# hurf1_board.net
KiCad netlist of a schematic drawn in EAGLE
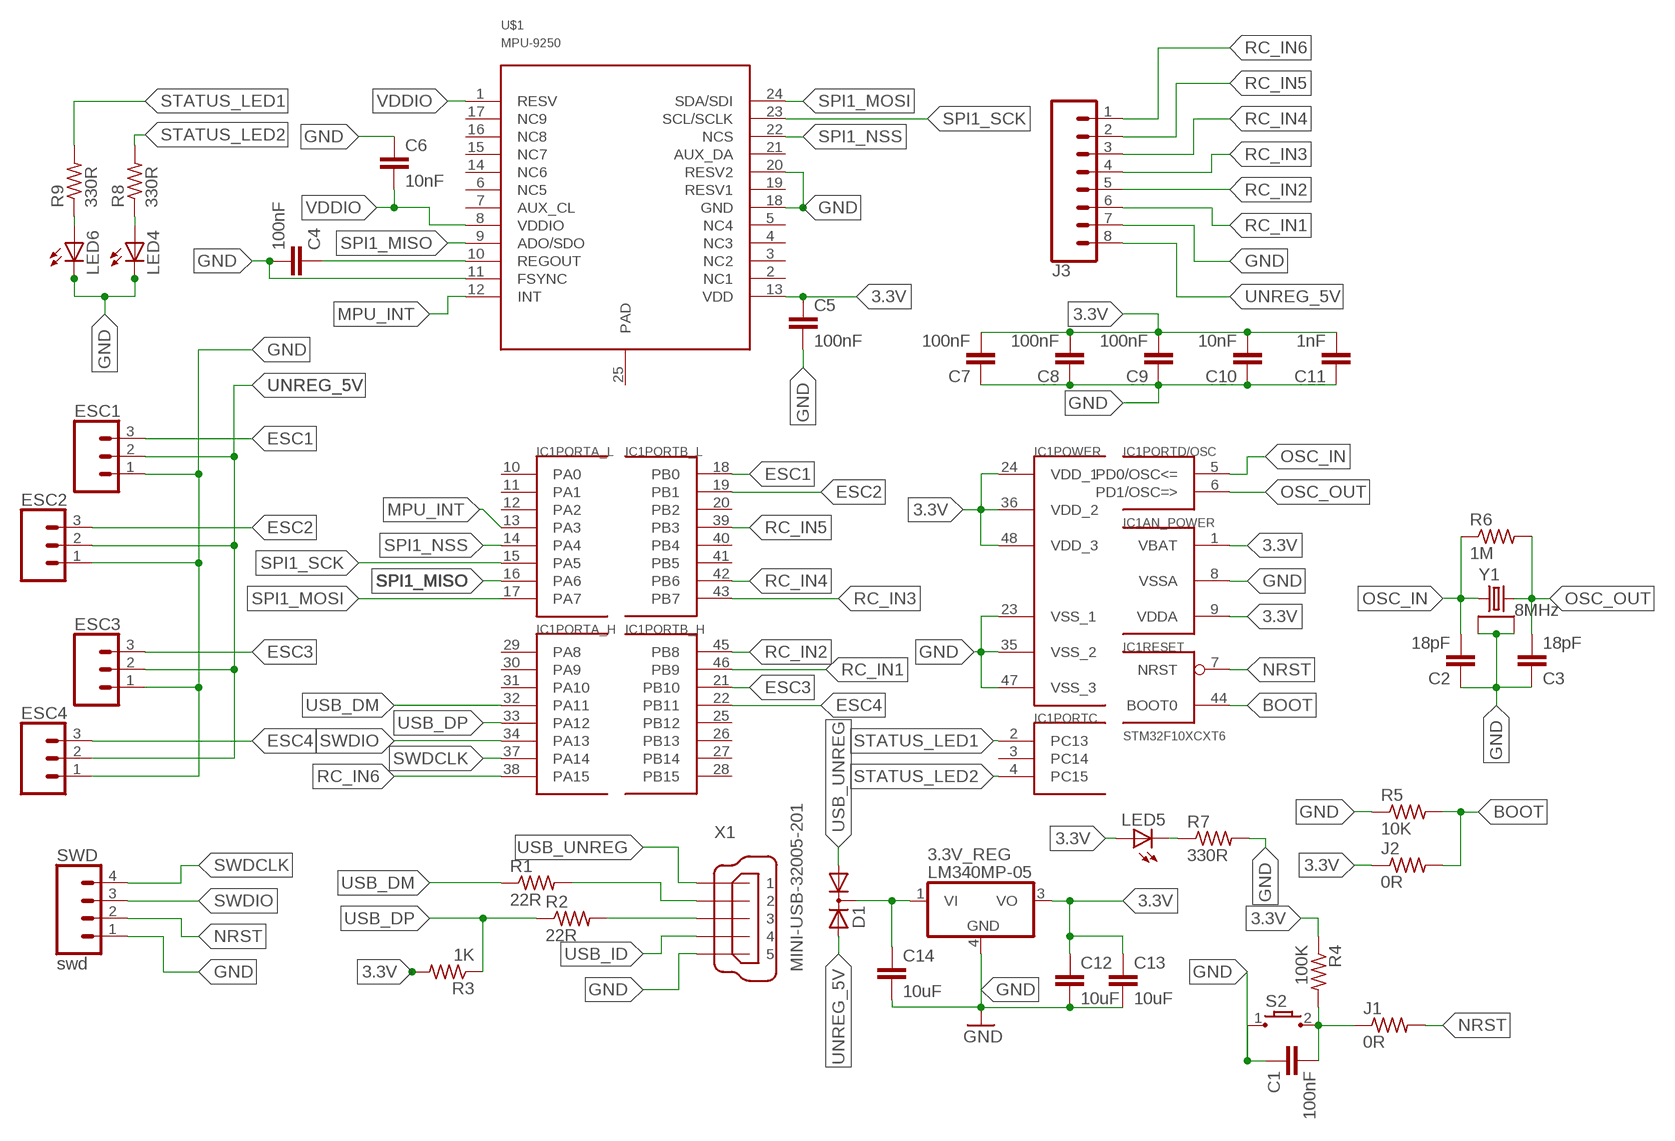
[diagram p0: schematic, sheet 1]

(export (version "E")
  (design (tool "Eeschema 10.0.6"))
  (components
    (comp (ref "3.3V_REG")
      (value "LM340MP-05")
      (footprint "eagle-import:SOT223")
      (libsource (lib "eagle-import") (part "LM340?-MP05"))
    )
    (comp (ref "C1")
      (value "100nF")
      (footprint "eagle-import:C0603")
      (libsource (lib "eagle-import") (part "C-EUC0603"))
    )
    (comp (ref "C2")
      (value "18pF")
      (footprint "eagle-import:C0603")
      (libsource (lib "eagle-import") (part "C-EUC0603"))
    )
    (comp (ref "C3")
      (value "18pF")
      (footprint "eagle-import:C0603")
      (libsource (lib "eagle-import") (part "C-EUC0603"))
    )
    (comp (ref "C4")
      (value "100nF")
      (footprint "eagle-import:C0805K")
      (libsource (lib "eagle-import") (part "resistor_348_C-EUC0805K"))
    )
    (comp (ref "C5")
      (value "100nF")
      (footprint "eagle-import:C0603")
      (libsource (lib "eagle-import") (part "C-EUC0603"))
    )
    (comp (ref "C6")
      (value "10nF")
      (footprint "eagle-import:C0603")
      (libsource (lib "eagle-import") (part "C-EUC0603"))
    )
    (comp (ref "C7")
      (value "100nF")
      (footprint "eagle-import:C0603")
      (libsource (lib "eagle-import") (part "C-EUC0603"))
    )
    (comp (ref "C8")
      (value "100nF")
      (footprint "eagle-import:C0603")
      (libsource (lib "eagle-import") (part "C-EUC0603"))
    )
    (comp (ref "C9")
      (value "100nF")
      (footprint "eagle-import:C0603")
      (libsource (lib "eagle-import") (part "C-EUC0603"))
    )
    (comp (ref "C10")
      (value "10nF")
      (footprint "eagle-import:C0603")
      (libsource (lib "eagle-import") (part "C-EUC0603"))
    )
    (comp (ref "C11")
      (value "1nF")
      (footprint "eagle-import:C0603")
      (libsource (lib "eagle-import") (part "C-EUC0603"))
    )
    (comp (ref "C12")
      (value "10uF")
      (footprint "eagle-import:C0805")
      (libsource (lib "eagle-import") (part "C-EUC0805"))
    )
    (comp (ref "C13")
      (value "10uF")
      (footprint "eagle-import:C0805")
      (libsource (lib "eagle-import") (part "C-EUC0805"))
    )
    (comp (ref "C14")
      (value "10uF")
      (footprint "eagle-import:C0805")
      (libsource (lib "eagle-import") (part "C-EUC0805"))
    )
    (comp (ref "D1")
      (value "DIODE-2AC|CASOT23")
      (footprint "eagle-import:SOT23")
      (libsource (lib "eagle-import") (part "DIODE-2AC|CASOT23"))
    )
    (comp (ref "ESC1")
      (value "CONN_03")
      (footprint "eagle-import:1X03")
      (libsource (lib "eagle-import") (part "CONN_03"))
    )
    (comp (ref "ESC2")
      (value "CONN_03")
      (footprint "eagle-import:1X03")
      (libsource (lib "eagle-import") (part "CONN_03"))
    )
    (comp (ref "ESC3")
      (value "CONN_03")
      (footprint "eagle-import:1X03")
      (libsource (lib "eagle-import") (part "CONN_03"))
    )
    (comp (ref "ESC4")
      (value "CONN_03")
      (footprint "eagle-import:1X03")
      (libsource (lib "eagle-import") (part "CONN_03"))
    )
    (comp (ref "IC1")
      (value "STM32F10XCXT6")
      (footprint "eagle-import:TQFP48")
      (libsource (lib "eagle-import") (part "STM32F10XCXT6"))
    )
    (comp (ref "J1")
      (value "0R")
      (footprint "eagle-import:R0603")
      (libsource (lib "eagle-import") (part "R-US_R0603"))
    )
    (comp (ref "J2")
      (value "0R")
      (footprint "eagle-import:R0603")
      (libsource (lib "eagle-import") (part "R-US_R0603"))
    )
    (comp (ref "J3")
      (value "CONN_08")
      (footprint "eagle-import:1X08_1MM_RA")
      (libsource (lib "eagle-import") (part "CONN_08"))
    )
    (comp (ref "LED4")
      (value "LEDSML0805")
      (footprint "eagle-import:SML0805")
      (libsource (lib "eagle-import") (part "LEDSML0805"))
    )
    (comp (ref "LED5")
      (value "LEDSML0805")
      (footprint "eagle-import:SML0805")
      (libsource (lib "eagle-import") (part "LEDSML0805"))
    )
    (comp (ref "LED6")
      (value "LEDSML0805")
      (footprint "eagle-import:SML0805")
      (libsource (lib "eagle-import") (part "LEDSML0805"))
    )
    (comp (ref "R1")
      (value "22R")
      (footprint "eagle-import:R0603")
      (libsource (lib "eagle-import") (part "R-US_R0603"))
    )
    (comp (ref "R2")
      (value "22R")
      (footprint "eagle-import:R0603")
      (libsource (lib "eagle-import") (part "R-US_R0603"))
    )
    (comp (ref "R3")
      (value "1K")
      (footprint "eagle-import:R0603")
      (libsource (lib "eagle-import") (part "R-US_R0603"))
    )
    (comp (ref "R4")
      (value "100K")
      (footprint "eagle-import:R0603")
      (libsource (lib "eagle-import") (part "R-US_R0603"))
    )
    (comp (ref "R5")
      (value "10K")
      (footprint "eagle-import:R0603")
      (libsource (lib "eagle-import") (part "R-US_R0603"))
    )
    (comp (ref "R6")
      (value "1M")
      (footprint "eagle-import:R0603")
      (libsource (lib "eagle-import") (part "R-US_R0603"))
    )
    (comp (ref "R7")
      (value "330R")
      (footprint "eagle-import:R0603")
      (libsource (lib "eagle-import") (part "R-US_R0603"))
    )
    (comp (ref "R8")
      (value "330R")
      (footprint "eagle-import:R0603")
      (libsource (lib "eagle-import") (part "R-US_R0603"))
    )
    (comp (ref "R9")
      (value "330R")
      (footprint "eagle-import:R0603")
      (libsource (lib "eagle-import") (part "R-US_R0603"))
    )
    (comp (ref "S2")
      (value "TL3302-G")
      (footprint "eagle-import:TL3302_GULL_WING")
      (libsource (lib "eagle-import") (part "TL3302-G"))
    )
    (comp (ref "SWD")
      (value "swd")
      (footprint "eagle-import:1X04_1MM_RA")
      (libsource (lib "eagle-import") (part "CONN_04SMD2"))
    )
    (comp (ref "U$1")
      (value "MPU-9250")
      (footprint "eagle-import:LEAD-QFN24")
      (libsource (lib "eagle-import") (part "MPU-9250"))
    )
    (comp (ref "X1")
      (value "MINI-USB-32005-201")
      (footprint "eagle-import:32005-201")
      (libsource (lib "eagle-import") (part "MINI-USB-32005-201"))
    )
    (comp (ref "Y1")
      (value "8MHz")
      (footprint "eagle-import:GSX-531")
      (libsource (lib "eagle-import") (part "GSX-531"))
    )
  )
  (nets
    (net (code "1") (name "3.3V") (class "Default")
      (node (ref "3.3V_REG") (pin "3") (pinfunction "VO_3") (pintype "passive"))
      (node (ref "C10") (pin "2") (pinfunction "2_2") (pintype "passive"))
      (node (ref "C11") (pin "2") (pinfunction "2_2") (pintype "passive"))
      (node (ref "C12") (pin "1") (pinfunction "1_1") (pintype "passive"))
      (node (ref "C13") (pin "1") (pinfunction "1_1") (pintype "passive"))
      (node (ref "C5") (pin "1") (pinfunction "1_1") (pintype "passive"))
      (node (ref "C7") (pin "2") (pinfunction "2_2") (pintype "passive"))
      (node (ref "C8") (pin "2") (pinfunction "2_2") (pintype "passive"))
      (node (ref "C9") (pin "2") (pinfunction "2_2") (pintype "passive"))
      (node (ref "IC1") (pin "1") (pinfunction "VBAT_1") (pintype "power_in"))
      (node (ref "IC1") (pin "24") (pinfunction "VDD_1_24") (pintype "power_in"))
      (node (ref "IC1") (pin "36") (pinfunction "VDD_2_36") (pintype "power_in"))
      (node (ref "IC1") (pin "48") (pinfunction "VDD_3_48") (pintype "power_in"))
      (node (ref "IC1") (pin "9") (pinfunction "VDDA_9") (pintype "power_in"))
      (node (ref "J2") (pin "1") (pinfunction "1_1") (pintype "passive"))
      (node (ref "LED5") (pin "A") (pinfunction "A_A") (pintype "passive"))
      (node (ref "R3") (pin "2") (pinfunction "2_2") (pintype "passive"))
      (node (ref "R4") (pin "1") (pinfunction "1_1") (pintype "passive"))
      (node (ref "U$1") (pin "13") (pinfunction "VDD_13") (pintype "bidirectional"))
    )
    (net (code "2") (name "BOOT") (class "Default")
      (node (ref "IC1") (pin "44") (pinfunction "BOOT0_44") (pintype "input"))
      (node (ref "J2") (pin "2") (pinfunction "2_2") (pintype "passive"))
      (node (ref "R5") (pin "2") (pinfunction "2_2") (pintype "passive"))
    )
    (net (code "3") (name "ESC1") (class "Default")
      (node (ref "ESC1") (pin "3") (pinfunction "3_3") (pintype "passive"))
      (node (ref "IC1") (pin "18") (pinfunction "PB0_18") (pintype "bidirectional"))
    )
    (net (code "4") (name "ESC2") (class "Default")
      (node (ref "ESC2") (pin "3") (pinfunction "3_3") (pintype "passive"))
      (node (ref "IC1") (pin "19") (pinfunction "PB1_19") (pintype "bidirectional"))
    )
    (net (code "5") (name "ESC3") (class "Default")
      (node (ref "ESC3") (pin "3") (pinfunction "3_3") (pintype "passive"))
      (node (ref "IC1") (pin "21") (pinfunction "PB10_21") (pintype "bidirectional"))
    )
    (net (code "6") (name "ESC4") (class "Default")
      (node (ref "ESC4") (pin "3") (pinfunction "3_3") (pintype "passive"))
      (node (ref "IC1") (pin "22") (pinfunction "PB11_22") (pintype "bidirectional"))
    )
    (net (code "7") (name "GND") (class "Default")
      (node (ref "3.3V_REG") (pin "4") (pinfunction "GND_4") (pintype "passive"))
      (node (ref "C1") (pin "1") (pinfunction "1_1") (pintype "passive"))
      (node (ref "C10") (pin "1") (pinfunction "1_1") (pintype "passive"))
      (node (ref "C11") (pin "1") (pinfunction "1_1") (pintype "passive"))
      (node (ref "C12") (pin "2") (pinfunction "2_2") (pintype "passive"))
      (node (ref "C13") (pin "2") (pinfunction "2_2") (pintype "passive"))
      (node (ref "C14") (pin "2") (pinfunction "2_2") (pintype "passive"))
      (node (ref "C2") (pin "1") (pinfunction "1_1") (pintype "passive"))
      (node (ref "C3") (pin "1") (pinfunction "1_1") (pintype "passive"))
      (node (ref "C4") (pin "2") (pinfunction "2_2") (pintype "passive"))
      (node (ref "C5") (pin "2") (pinfunction "2_2") (pintype "passive"))
      (node (ref "C6") (pin "1") (pinfunction "1_1") (pintype "passive"))
      (node (ref "C7") (pin "1") (pinfunction "1_1") (pintype "passive"))
      (node (ref "C8") (pin "1") (pinfunction "1_1") (pintype "passive"))
      (node (ref "C9") (pin "1") (pinfunction "1_1") (pintype "passive"))
      (node (ref "ESC1") (pin "1") (pinfunction "1_1") (pintype "passive"))
      (node (ref "ESC2") (pin "1") (pinfunction "1_1") (pintype "passive"))
      (node (ref "ESC3") (pin "1") (pinfunction "1_1") (pintype "passive"))
      (node (ref "ESC4") (pin "1") (pinfunction "1_1") (pintype "passive"))
      (node (ref "IC1") (pin "23") (pinfunction "VSS_1_23") (pintype "power_in"))
      (node (ref "IC1") (pin "35") (pinfunction "VSS_2_35") (pintype "power_in"))
      (node (ref "IC1") (pin "47") (pinfunction "VSS_3_47") (pintype "power_in"))
      (node (ref "IC1") (pin "8") (pinfunction "VSSA_8") (pintype "power_in"))
      (node (ref "J3") (pin "7") (pinfunction "7_7") (pintype "passive"))
      (node (ref "LED4") (pin "C") (pinfunction "C_C") (pintype "passive"))
      (node (ref "LED6") (pin "C") (pinfunction "C_C") (pintype "passive"))
      (node (ref "R5") (pin "1") (pinfunction "1_1") (pintype "passive"))
      (node (ref "R7") (pin "2") (pinfunction "2_2") (pintype "passive"))
      (node (ref "S2") (pin "1") (pinfunction "1_1") (pintype "passive"))
      (node (ref "SWD") (pin "1") (pinfunction "1_1") (pintype "passive"))
      (node (ref "U$1") (pin "11") (pinfunction "FSYNC_11") (pintype "bidirectional"))
      (node (ref "U$1") (pin "18") (pinfunction "GND_18") (pintype "bidirectional"))
      (node (ref "U$1") (pin "20") (pinfunction "RESV2_20") (pintype "bidirectional"))
      (node (ref "X1") (pin "5") (pinfunction "5_5") (pintype "passive"))
      (node (ref "Y1") (pin "2") (pinfunction "2_2") (pintype "passive"))
      (node (ref "Y1") (pin "4") (pinfunction "4_4") (pintype "passive"))
    )
    (net (code "8") (name "MPU_INT") (class "Default")
      (node (ref "IC1") (pin "13") (pinfunction "PA3_13") (pintype "bidirectional"))
      (node (ref "U$1") (pin "12") (pinfunction "INT_12") (pintype "bidirectional"))
    )
    (net (code "9") (name "NRST") (class "Default")
      (node (ref "IC1") (pin "7") (pinfunction "NRST_7") (pintype "input"))
      (node (ref "J1") (pin "2") (pinfunction "2_2") (pintype "passive"))
      (node (ref "SWD") (pin "2") (pinfunction "2_2") (pintype "passive"))
    )
    (net (code "10") (name "Net-(3.3V_REG-VI)") (class "Default")
      (node (ref "3.3V_REG") (pin "1") (pinfunction "VI_1") (pintype "input"))
      (node (ref "C14") (pin "1") (pinfunction "1_1") (pintype "passive"))
      (node (ref "D1") (pin "3") (pinfunction "C_3") (pintype "passive"))
    )
    (net (code "11") (name "Net-(C1-Pad2)") (class "Default")
      (node (ref "C1") (pin "2") (pinfunction "2_2") (pintype "passive"))
      (node (ref "J1") (pin "1") (pinfunction "1_1") (pintype "passive"))
      (node (ref "R4") (pin "2") (pinfunction "2_2") (pintype "passive"))
      (node (ref "S2") (pin "2") (pinfunction "2_2") (pintype "passive"))
    )
    (net (code "12") (name "Net-(LED4-PadA)") (class "Default")
      (node (ref "LED4") (pin "A") (pinfunction "A_A") (pintype "passive"))
      (node (ref "R8") (pin "1") (pinfunction "1_1") (pintype "passive"))
    )
    (net (code "13") (name "Net-(LED5-PadC)") (class "Default")
      (node (ref "LED5") (pin "C") (pinfunction "C_C") (pintype "passive"))
      (node (ref "R7") (pin "1") (pinfunction "1_1") (pintype "passive"))
    )
    (net (code "14") (name "Net-(LED6-PadA)") (class "Default")
      (node (ref "LED6") (pin "A") (pinfunction "A_A") (pintype "passive"))
      (node (ref "R9") (pin "1") (pinfunction "1_1") (pintype "passive"))
    )
    (net (code "15") (name "Net-(R1-Pad2)") (class "Default")
      (node (ref "R1") (pin "2") (pinfunction "2_2") (pintype "passive"))
      (node (ref "X1") (pin "2") (pinfunction "2_2") (pintype "passive"))
    )
    (net (code "16") (name "Net-(R2-Pad2)") (class "Default")
      (node (ref "R2") (pin "2") (pinfunction "2_2") (pintype "passive"))
      (node (ref "X1") (pin "3") (pinfunction "3_3") (pintype "passive"))
    )
    (net (code "17") (name "Net-(U$1-REGOUT)") (class "Default")
      (node (ref "C4") (pin "1") (pinfunction "1_1") (pintype "passive"))
      (node (ref "U$1") (pin "10") (pinfunction "REGOUT_10") (pintype "bidirectional"))
    )
    (net (code "18") (name "OSC_IN") (class "Default")
      (node (ref "C2") (pin "2") (pinfunction "2_2") (pintype "passive"))
      (node (ref "IC1") (pin "5") (pinfunction "PD0/OSC<=_5") (pintype "bidirectional"))
      (node (ref "R6") (pin "1") (pinfunction "1_1") (pintype "passive"))
      (node (ref "Y1") (pin "1") (pinfunction "1_1") (pintype "passive"))
    )
    (net (code "19") (name "OSC_OUT") (class "Default")
      (node (ref "C3") (pin "2") (pinfunction "2_2") (pintype "passive"))
      (node (ref "IC1") (pin "6") (pinfunction "PD1/OSC=>_6") (pintype "bidirectional"))
      (node (ref "R6") (pin "2") (pinfunction "2_2") (pintype "passive"))
      (node (ref "Y1") (pin "3") (pinfunction "3_3") (pintype "passive"))
    )
    (net (code "20") (name "RC_IN1") (class "Default")
      (node (ref "IC1") (pin "46") (pinfunction "PB9_46") (pintype "bidirectional"))
      (node (ref "J3") (pin "6") (pinfunction "6_6") (pintype "passive"))
    )
    (net (code "21") (name "RC_IN2") (class "Default")
      (node (ref "IC1") (pin "45") (pinfunction "PB8_45") (pintype "bidirectional"))
      (node (ref "J3") (pin "5") (pinfunction "5_5") (pintype "passive"))
    )
    (net (code "22") (name "RC_IN3") (class "Default")
      (node (ref "IC1") (pin "43") (pinfunction "PB7_43") (pintype "bidirectional"))
      (node (ref "J3") (pin "4") (pinfunction "4_4") (pintype "passive"))
    )
    (net (code "23") (name "RC_IN4") (class "Default")
      (node (ref "IC1") (pin "42") (pinfunction "PB6_42") (pintype "bidirectional"))
      (node (ref "J3") (pin "3") (pinfunction "3_3") (pintype "passive"))
    )
    (net (code "24") (name "RC_IN5") (class "Default")
      (node (ref "IC1") (pin "39") (pinfunction "PB3_39") (pintype "bidirectional"))
      (node (ref "J3") (pin "2") (pinfunction "2_2") (pintype "passive"))
    )
    (net (code "25") (name "RC_IN6") (class "Default")
      (node (ref "IC1") (pin "38") (pinfunction "PA15_38") (pintype "bidirectional"))
      (node (ref "J3") (pin "1") (pinfunction "1_1") (pintype "passive"))
    )
    (net (code "26") (name "SPI1_MISO") (class "Default")
      (node (ref "IC1") (pin "16") (pinfunction "PA6_16") (pintype "bidirectional"))
      (node (ref "U$1") (pin "9") (pinfunction "ADO/SDO_9") (pintype "bidirectional"))
    )
    (net (code "27") (name "SPI1_MOSI") (class "Default")
      (node (ref "IC1") (pin "17") (pinfunction "PA7_17") (pintype "bidirectional"))
      (node (ref "U$1") (pin "24") (pinfunction "SDA/SDI_24") (pintype "bidirectional"))
    )
    (net (code "28") (name "SPI1_NSS") (class "Default")
      (node (ref "IC1") (pin "14") (pinfunction "PA4_14") (pintype "bidirectional"))
      (node (ref "U$1") (pin "22") (pinfunction "NCS_22") (pintype "bidirectional"))
    )
    (net (code "29") (name "SPI1_SCK") (class "Default")
      (node (ref "IC1") (pin "15") (pinfunction "PA5_15") (pintype "bidirectional"))
      (node (ref "U$1") (pin "23") (pinfunction "SCL/SCLK_23") (pintype "bidirectional"))
    )
    (net (code "30") (name "STATUS_LED1") (class "Default")
      (node (ref "IC1") (pin "2") (pinfunction "PC13_2") (pintype "bidirectional"))
      (node (ref "R9") (pin "2") (pinfunction "2_2") (pintype "passive"))
    )
    (net (code "31") (name "STATUS_LED2") (class "Default")
      (node (ref "IC1") (pin "4") (pinfunction "PC15_4") (pintype "bidirectional"))
      (node (ref "R8") (pin "2") (pinfunction "2_2") (pintype "passive"))
    )
    (net (code "32") (name "SWDCLK") (class "Default")
      (node (ref "IC1") (pin "37") (pinfunction "PA14_37") (pintype "bidirectional"))
      (node (ref "SWD") (pin "4") (pinfunction "4_4") (pintype "passive"))
    )
    (net (code "33") (name "SWDIO") (class "Default")
      (node (ref "IC1") (pin "34") (pinfunction "PA13_34") (pintype "bidirectional"))
      (node (ref "SWD") (pin "3") (pinfunction "3_3") (pintype "passive"))
    )
    (net (code "34") (name "UNREG_5V") (class "Default")
      (node (ref "D1") (pin "2") (pinfunction "A2_2") (pintype "passive"))
      (node (ref "ESC1") (pin "2") (pinfunction "2_2") (pintype "passive"))
      (node (ref "ESC2") (pin "2") (pinfunction "2_2") (pintype "passive"))
      (node (ref "ESC3") (pin "2") (pinfunction "2_2") (pintype "passive"))
      (node (ref "ESC4") (pin "2") (pinfunction "2_2") (pintype "passive"))
      (node (ref "J3") (pin "8") (pinfunction "8_8") (pintype "passive"))
    )
    (net (code "35") (name "USB_DM") (class "Default")
      (node (ref "IC1") (pin "32") (pinfunction "PA11_32") (pintype "bidirectional"))
      (node (ref "R1") (pin "1") (pinfunction "1_1") (pintype "passive"))
    )
    (net (code "36") (name "USB_DP") (class "Default")
      (node (ref "IC1") (pin "33") (pinfunction "PA12_33") (pintype "bidirectional"))
      (node (ref "R2") (pin "1") (pinfunction "1_1") (pintype "passive"))
      (node (ref "R3") (pin "1") (pinfunction "1_1") (pintype "passive"))
    )
    (net (code "37") (name "USB_ID") (class "Default")
      (node (ref "X1") (pin "4") (pinfunction "4_4") (pintype "passive"))
    )
    (net (code "38") (name "USB_UNREG") (class "Default")
      (node (ref "D1") (pin "1") (pinfunction "A1_1") (pintype "passive"))
      (node (ref "X1") (pin "1") (pinfunction "1_1") (pintype "passive"))
    )
    (net (code "39") (name "VDDIO") (class "Default")
      (node (ref "C6") (pin "2") (pinfunction "2_2") (pintype "passive"))
      (node (ref "U$1") (pin "1") (pinfunction "RESV_1") (pintype "bidirectional"))
      (node (ref "U$1") (pin "8") (pinfunction "VDDIO_8") (pintype "bidirectional"))
    )
    (net (code "40") (name "unconnected-(IC1B-PA8-Pad29)") (class "Default")
      (node (ref "IC1") (pin "29") (pinfunction "PA8_29") (pintype "bidirectional"))
    )
    (net (code "41") (name "unconnected-(IC1B-PA9-Pad30)") (class "Default")
      (node (ref "IC1") (pin "30") (pinfunction "PA9_30") (pintype "bidirectional"))
    )
    (net (code "42") (name "unconnected-(IC1B-PA10-Pad31)") (class "Default")
      (node (ref "IC1") (pin "31") (pinfunction "PA10_31") (pintype "bidirectional"))
    )
    (net (code "43") (name "unconnected-(IC1C-PA0-Pad10)") (class "Default")
      (node (ref "IC1") (pin "10") (pinfunction "PA0_10") (pintype "bidirectional"))
    )
    (net (code "44") (name "unconnected-(IC1C-PA1-Pad11)") (class "Default")
      (node (ref "IC1") (pin "11") (pinfunction "PA1_11") (pintype "bidirectional"))
    )
    (net (code "45") (name "unconnected-(IC1C-PA2-Pad12)") (class "Default")
      (node (ref "IC1") (pin "12") (pinfunction "PA2_12") (pintype "bidirectional"))
    )
    (net (code "46") (name "unconnected-(IC1D-PB12-Pad25)") (class "Default")
      (node (ref "IC1") (pin "25") (pinfunction "PB12_25") (pintype "bidirectional"))
    )
    (net (code "47") (name "unconnected-(IC1D-PB13-Pad26)") (class "Default")
      (node (ref "IC1") (pin "26") (pinfunction "PB13_26") (pintype "bidirectional"))
    )
    (net (code "48") (name "unconnected-(IC1D-PB14-Pad27)") (class "Default")
      (node (ref "IC1") (pin "27") (pinfunction "PB14_27") (pintype "bidirectional"))
    )
    (net (code "49") (name "unconnected-(IC1D-PB15-Pad28)") (class "Default")
      (node (ref "IC1") (pin "28") (pinfunction "PB15_28") (pintype "bidirectional"))
    )
    (net (code "50") (name "unconnected-(IC1E-PB2-Pad20)") (class "Default")
      (node (ref "IC1") (pin "20") (pinfunction "PB2_20") (pintype "bidirectional"))
    )
    (net (code "51") (name "unconnected-(IC1E-PB4-Pad40)") (class "Default")
      (node (ref "IC1") (pin "40") (pinfunction "PB4_40") (pintype "bidirectional"))
    )
    (net (code "52") (name "unconnected-(IC1E-PB5-Pad41)") (class "Default")
      (node (ref "IC1") (pin "41") (pinfunction "PB5_41") (pintype "bidirectional"))
    )
    (net (code "53") (name "unconnected-(IC1F-PC14-Pad3)") (class "Default")
      (node (ref "IC1") (pin "3") (pinfunction "PC14_3") (pintype "bidirectional"))
    )
    (net (code "54") (name "unconnected-(U$1-AUX_CL-Pad7)") (class "Default")
      (node (ref "U$1") (pin "7") (pinfunction "AUX_CL_7") (pintype "bidirectional"))
    )
    (net (code "55") (name "unconnected-(U$1-AUX_DA-Pad21)") (class "Default")
      (node (ref "U$1") (pin "21") (pinfunction "AUX_DA_21") (pintype "bidirectional"))
    )
    (net (code "56") (name "unconnected-(U$1-NC1-Pad2)") (class "Default")
      (node (ref "U$1") (pin "2") (pinfunction "NC1_2") (pintype "bidirectional"))
    )
    (net (code "57") (name "unconnected-(U$1-NC2-Pad3)") (class "Default")
      (node (ref "U$1") (pin "3") (pinfunction "NC2_3") (pintype "bidirectional"))
    )
    (net (code "58") (name "unconnected-(U$1-NC3-Pad4)") (class "Default")
      (node (ref "U$1") (pin "4") (pinfunction "NC3_4") (pintype "bidirectional"))
    )
    (net (code "59") (name "unconnected-(U$1-NC4-Pad5)") (class "Default")
      (node (ref "U$1") (pin "5") (pinfunction "NC4_5") (pintype "bidirectional"))
    )
    (net (code "60") (name "unconnected-(U$1-NC5-Pad6)") (class "Default")
      (node (ref "U$1") (pin "6") (pinfunction "NC5_6") (pintype "bidirectional"))
    )
    (net (code "61") (name "unconnected-(U$1-NC6-Pad14)") (class "Default")
      (node (ref "U$1") (pin "14") (pinfunction "NC6_14") (pintype "bidirectional"))
    )
    (net (code "62") (name "unconnected-(U$1-NC7-Pad15)") (class "Default")
      (node (ref "U$1") (pin "15") (pinfunction "NC7_15") (pintype "bidirectional"))
    )
    (net (code "63") (name "unconnected-(U$1-NC8-Pad16)") (class "Default")
      (node (ref "U$1") (pin "16") (pinfunction "NC8_16") (pintype "bidirectional"))
    )
    (net (code "64") (name "unconnected-(U$1-NC9-Pad17)") (class "Default")
      (node (ref "U$1") (pin "17") (pinfunction "NC9_17") (pintype "bidirectional"))
    )
    (net (code "65") (name "unconnected-(U$1-PAD-Pad25)") (class "Default")
      (node (ref "U$1") (pin "25") (pinfunction "PAD_25") (pintype "bidirectional"))
    )
    (net (code "66") (name "unconnected-(U$1-RESV1-Pad19)") (class "Default")
      (node (ref "U$1") (pin "19") (pinfunction "RESV1_19") (pintype "bidirectional"))
    )
  )
)
